# Controllboard.net
KiCad netlist of a schematic drawn in EAGLE
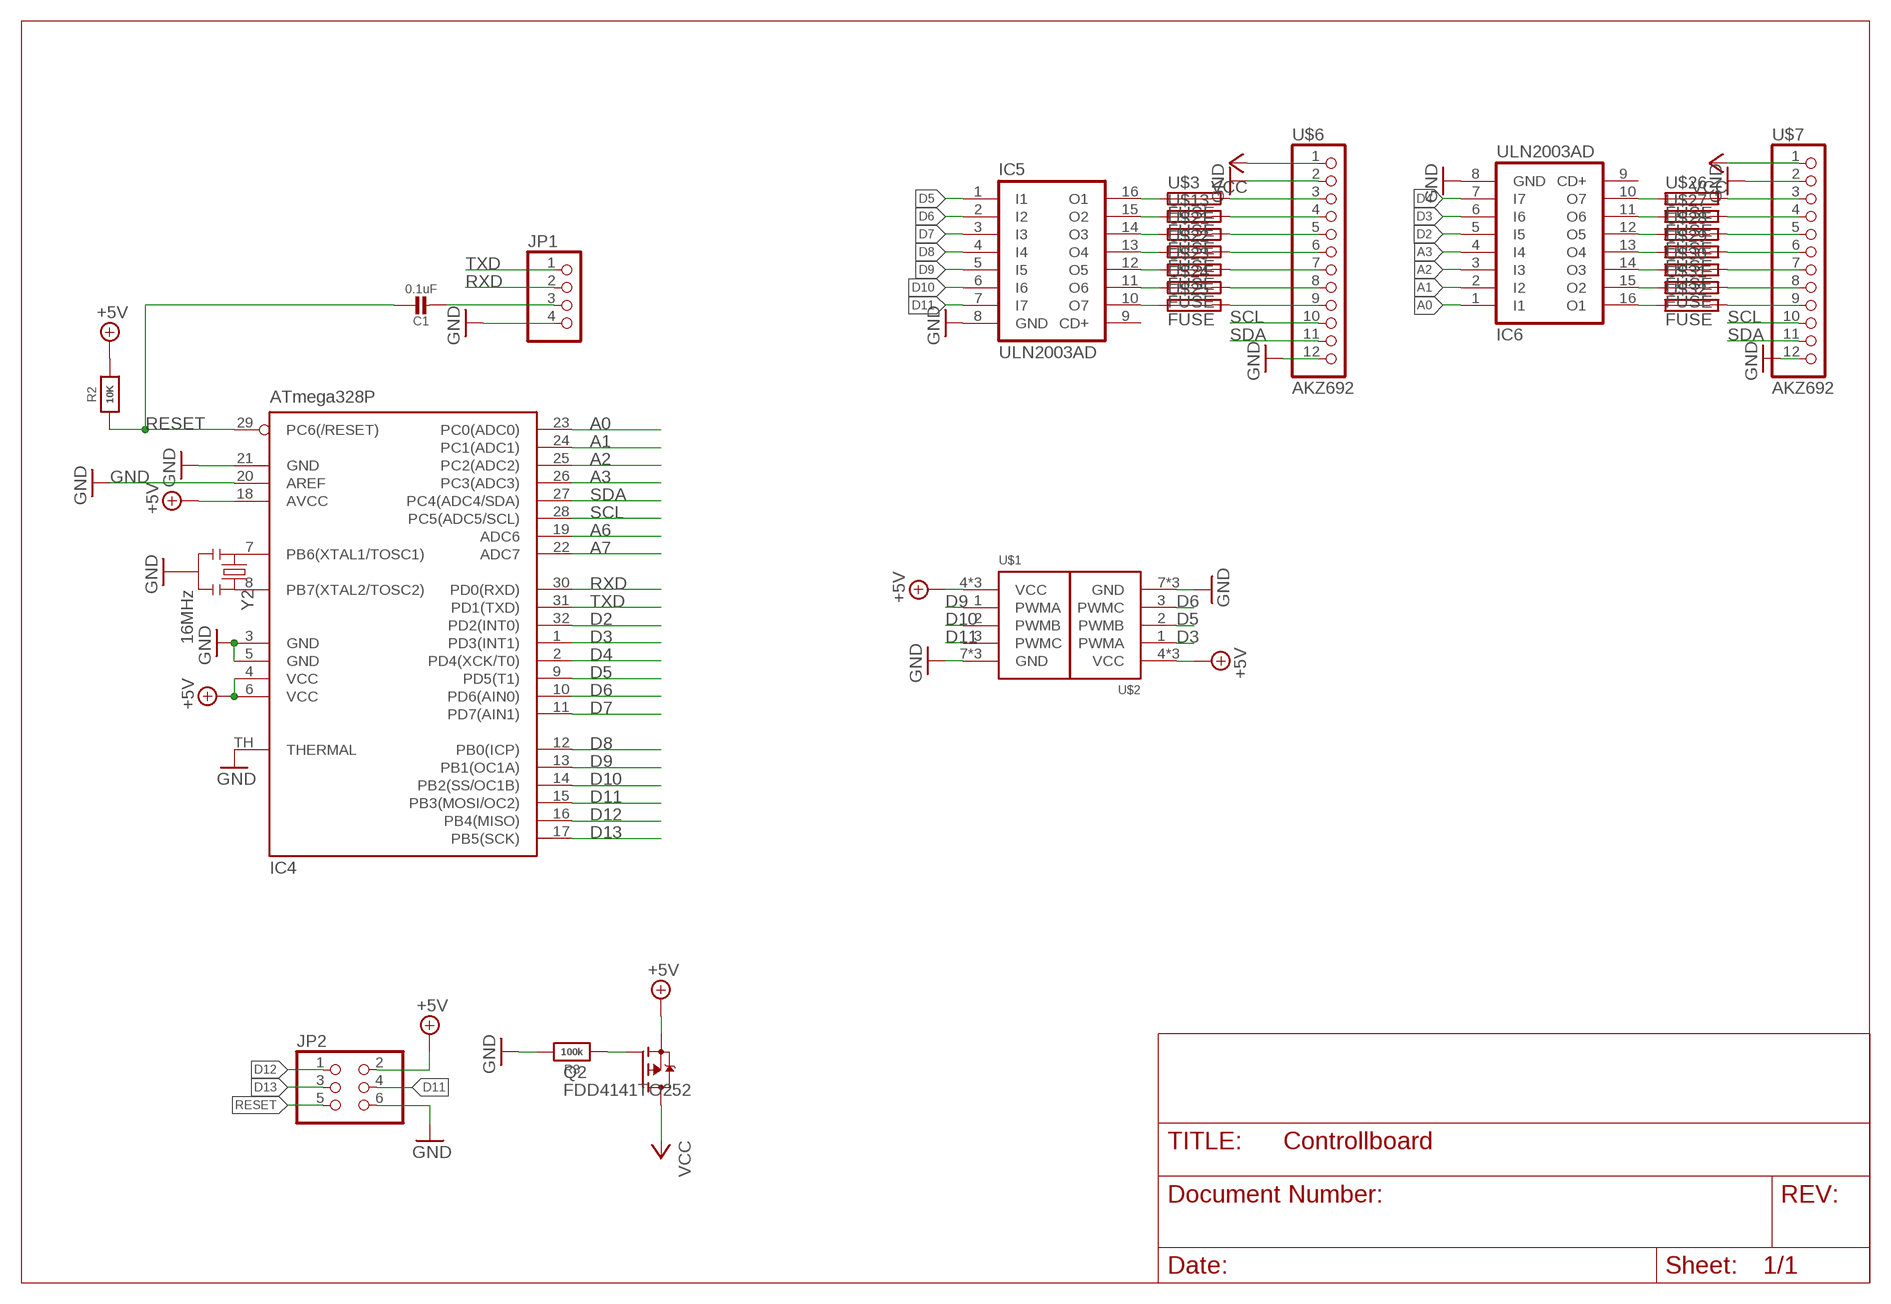
[diagram p0: schematic, sheet 1]

(export (version "E")
  (design (tool "Eeschema 10.0.6"))
  (components
    (comp (ref "C1")
      (value "0.1uF")
      (footprint "eagle-import:0805-NO")
      (libsource (lib "eagle-import") (part "CAP_CERAMIC0805-NOOUTLINE"))
    )
    (comp (ref "IC4")
      (value "ATmega328P")
      (footprint "eagle-import:MLF32-TH")
      (fields (field (name "MPN") "ATMEGA88PA-MU"))
      (libsource (lib "eagle-import") (part "MEGA8-MI"))
    )
    (comp (ref "IC5")
      (value "ULN2003AD")
      (footprint "eagle-import:SO16")
      (libsource (lib "eagle-import") (part "ULN2003AD"))
    )
    (comp (ref "IC6")
      (value "ULN2003AD")
      (footprint "eagle-import:SO16")
      (libsource (lib "eagle-import") (part "ULN2003AD"))
    )
    (comp (ref "JP1")
      (value "PINHD-1X4")
      (footprint "eagle-import:1X04")
      (libsource (lib "eagle-import") (part "PINHD-1X4"))
    )
    (comp (ref "JP2")
      (value "PINHD-2X3M")
      (footprint "eagle-import:2X03M")
      (libsource (lib "eagle-import") (part "PINHD-2X3M"))
    )
    (comp (ref "Q2")
      (value "FDD4141TO252")
      (footprint "eagle-import:TO252")
      (libsource (lib "eagle-import") (part "FDD4141TO252"))
    )
    (comp (ref "R2")
      (value "10K")
      (footprint "eagle-import:0805-NO")
      (libsource (lib "eagle-import") (part "RESISTOR0805_NOOUTLINE"))
    )
    (comp (ref "R3")
      (value "100k")
      (footprint "eagle-import:0805-NO")
      (libsource (lib "eagle-import") (part "RESISTOR0805_NOOUTLINE"))
    )
    (comp (ref "U$1")
      (value "SERVO_X3")
      (footprint "eagle-import:2X03_90")
      (libsource (lib "eagle-import") (part "SERVO_X3"))
    )
    (comp (ref "U$2")
      (value "SERVO_X3")
      (footprint "eagle-import:2X03_90")
      (libsource (lib "eagle-import") (part "SERVO_X3"))
    )
    (comp (ref "U$3")
      (value "FUSE")
      (footprint "eagle-import:C1206")
      (libsource (lib "eagle-import") (part "FUSE"))
    )
    (comp (ref "U$6")
      (value "AKZ692")
      (footprint "eagle-import:1X12")
      (libsource (lib "eagle-import") (part "AKZ692"))
    )
    (comp (ref "U$7")
      (value "AKZ692")
      (footprint "eagle-import:1X12")
      (libsource (lib "eagle-import") (part "AKZ692"))
    )
    (comp (ref "U$13")
      (value "FUSE")
      (footprint "eagle-import:C1206")
      (libsource (lib "eagle-import") (part "FUSE"))
    )
    (comp (ref "U$21")
      (value "FUSE")
      (footprint "eagle-import:C1206")
      (libsource (lib "eagle-import") (part "FUSE"))
    )
    (comp (ref "U$22")
      (value "FUSE")
      (footprint "eagle-import:C1206")
      (libsource (lib "eagle-import") (part "FUSE"))
    )
    (comp (ref "U$23")
      (value "FUSE")
      (footprint "eagle-import:C1206")
      (libsource (lib "eagle-import") (part "FUSE"))
    )
    (comp (ref "U$24")
      (value "FUSE")
      (footprint "eagle-import:C1206")
      (libsource (lib "eagle-import") (part "FUSE"))
    )
    (comp (ref "U$25")
      (value "FUSE")
      (footprint "eagle-import:C1206")
      (libsource (lib "eagle-import") (part "FUSE"))
    )
    (comp (ref "U$26")
      (value "FUSE")
      (footprint "eagle-import:C1206")
      (libsource (lib "eagle-import") (part "FUSE"))
    )
    (comp (ref "U$27")
      (value "FUSE")
      (footprint "eagle-import:C1206")
      (libsource (lib "eagle-import") (part "FUSE"))
    )
    (comp (ref "U$28")
      (value "FUSE")
      (footprint "eagle-import:C1206")
      (libsource (lib "eagle-import") (part "FUSE"))
    )
    (comp (ref "U$29")
      (value "FUSE")
      (footprint "eagle-import:C1206")
      (libsource (lib "eagle-import") (part "FUSE"))
    )
    (comp (ref "U$30")
      (value "FUSE")
      (footprint "eagle-import:C1206")
      (libsource (lib "eagle-import") (part "FUSE"))
    )
    (comp (ref "U$31")
      (value "FUSE")
      (footprint "eagle-import:C1206")
      (libsource (lib "eagle-import") (part "FUSE"))
    )
    (comp (ref "U$32")
      (value "FUSE")
      (footprint "eagle-import:C1206")
      (libsource (lib "eagle-import") (part "FUSE"))
    )
    (comp (ref "Y2")
      (value "16MHz")
      (footprint "eagle-import:RESONATOR-SMD")
      (libsource (lib "eagle-import") (part "RESONATORSMD"))
    )
  )
  (nets
    (net (code "1") (name "+5V") (class "Default")
      (node (ref "IC4") (pin "18") (pinfunction "AVCC_18") (pintype "power_in"))
      (node (ref "IC4") (pin "4") (pinfunction "VCC_4") (pintype "power_in"))
      (node (ref "IC4") (pin "6") (pinfunction "VCC_6") (pintype "power_in"))
      (node (ref "JP2") (pin "2") (pinfunction "2_2") (pintype "passive"))
      (node (ref "Q2") (pin "2") (pinfunction "S_2") (pintype "passive"))
      (node (ref "R2") (pin "2") (pinfunction "2_2") (pintype "passive"))
      (node (ref "U$1") (pin "4") (pinfunction "VCC_4") (pintype "bidirectional"))
      (node (ref "U$1") (pin "5") (pinfunction "VCC_5") (pintype "bidirectional"))
      (node (ref "U$1") (pin "6") (pinfunction "VCC_6") (pintype "bidirectional"))
      (node (ref "U$2") (pin "4") (pinfunction "VCC_4") (pintype "bidirectional"))
      (node (ref "U$2") (pin "5") (pinfunction "VCC_5") (pintype "bidirectional"))
      (node (ref "U$2") (pin "6") (pinfunction "VCC_6") (pintype "bidirectional"))
    )
    (net (code "2") (name "/A6") (class "Default")
      (node (ref "IC4") (pin "19") (pinfunction "ADC6_19") (pintype "bidirectional"))
    )
    (net (code "3") (name "/A7") (class "Default")
      (node (ref "IC4") (pin "22") (pinfunction "ADC7_22") (pintype "bidirectional"))
    )
    (net (code "4") (name "/RXD") (class "Default")
      (node (ref "IC4") (pin "30") (pinfunction "PD0(RXD)_30") (pintype "bidirectional"))
      (node (ref "JP1") (pin "2") (pinfunction "2_2") (pintype "passive"))
    )
    (net (code "5") (name "/SCL") (class "Default")
      (node (ref "IC4") (pin "28") (pinfunction "PC5(ADC5/SCL)_28") (pintype "bidirectional"))
      (node (ref "U$6") (pin "10") (pinfunction "10_10") (pintype "passive"))
      (node (ref "U$7") (pin "10") (pinfunction "10_10") (pintype "passive"))
    )
    (net (code "6") (name "/SDA") (class "Default")
      (node (ref "IC4") (pin "27") (pinfunction "PC4(ADC4/SDA)_27") (pintype "bidirectional"))
      (node (ref "U$6") (pin "11") (pinfunction "11_11") (pintype "passive"))
      (node (ref "U$7") (pin "11") (pinfunction "11_11") (pintype "passive"))
    )
    (net (code "7") (name "/TXD") (class "Default")
      (node (ref "IC4") (pin "31") (pinfunction "PD1(TXD)_31") (pintype "bidirectional"))
      (node (ref "JP1") (pin "1") (pinfunction "1_1") (pintype "passive"))
    )
    (net (code "8") (name "A0") (class "Default")
      (node (ref "IC4") (pin "23") (pinfunction "PC0(ADC0)_23") (pintype "bidirectional"))
      (node (ref "IC6") (pin "1") (pinfunction "I1_1") (pintype "input"))
    )
    (net (code "9") (name "A1") (class "Default")
      (node (ref "IC4") (pin "24") (pinfunction "PC1(ADC1)_24") (pintype "bidirectional"))
      (node (ref "IC6") (pin "2") (pinfunction "I2_2") (pintype "input"))
    )
    (net (code "10") (name "A2") (class "Default")
      (node (ref "IC4") (pin "25") (pinfunction "PC2(ADC2)_25") (pintype "bidirectional"))
      (node (ref "IC6") (pin "3") (pinfunction "I3_3") (pintype "input"))
    )
    (net (code "11") (name "A3") (class "Default")
      (node (ref "IC4") (pin "26") (pinfunction "PC3(ADC3)_26") (pintype "bidirectional"))
      (node (ref "IC6") (pin "4") (pinfunction "I4_4") (pintype "input"))
    )
    (net (code "12") (name "D2") (class "Default")
      (node (ref "IC4") (pin "32") (pinfunction "PD2(INT0)_32") (pintype "bidirectional"))
      (node (ref "IC6") (pin "5") (pinfunction "I5_5") (pintype "input"))
    )
    (net (code "13") (name "D3") (class "Default")
      (node (ref "IC4") (pin "1") (pinfunction "PD3(INT1)_1") (pintype "bidirectional"))
      (node (ref "IC6") (pin "6") (pinfunction "I6_6") (pintype "input"))
      (node (ref "U$2") (pin "1") (pinfunction "PWMA_1") (pintype "bidirectional"))
    )
    (net (code "14") (name "D4") (class "Default")
      (node (ref "IC4") (pin "2") (pinfunction "PD4(XCK/T0)_2") (pintype "bidirectional"))
      (node (ref "IC6") (pin "7") (pinfunction "I7_7") (pintype "input"))
    )
    (net (code "15") (name "D5") (class "Default")
      (node (ref "IC4") (pin "9") (pinfunction "PD5(T1)_9") (pintype "bidirectional"))
      (node (ref "IC5") (pin "1") (pinfunction "I1_1") (pintype "input"))
      (node (ref "U$2") (pin "2") (pinfunction "PWMB_2") (pintype "bidirectional"))
    )
    (net (code "16") (name "D6") (class "Default")
      (node (ref "IC4") (pin "10") (pinfunction "PD6(AIN0)_10") (pintype "bidirectional"))
      (node (ref "IC5") (pin "2") (pinfunction "I2_2") (pintype "input"))
      (node (ref "U$2") (pin "3") (pinfunction "PWMC_3") (pintype "bidirectional"))
    )
    (net (code "17") (name "D7") (class "Default")
      (node (ref "IC4") (pin "11") (pinfunction "PD7(AIN1)_11") (pintype "bidirectional"))
      (node (ref "IC5") (pin "3") (pinfunction "I3_3") (pintype "input"))
    )
    (net (code "18") (name "D8") (class "Default")
      (node (ref "IC4") (pin "12") (pinfunction "PB0(ICP)_12") (pintype "bidirectional"))
      (node (ref "IC5") (pin "4") (pinfunction "I4_4") (pintype "input"))
    )
    (net (code "19") (name "D9") (class "Default")
      (node (ref "IC4") (pin "13") (pinfunction "PB1(OC1A)_13") (pintype "bidirectional"))
      (node (ref "IC5") (pin "5") (pinfunction "I5_5") (pintype "input"))
      (node (ref "U$1") (pin "1") (pinfunction "PWMA_1") (pintype "bidirectional"))
    )
    (net (code "20") (name "D10") (class "Default")
      (node (ref "IC4") (pin "14") (pinfunction "PB2(SS/OC1B)_14") (pintype "bidirectional"))
      (node (ref "IC5") (pin "6") (pinfunction "I6_6") (pintype "input"))
      (node (ref "U$1") (pin "2") (pinfunction "PWMB_2") (pintype "bidirectional"))
    )
    (net (code "21") (name "D11") (class "Default")
      (node (ref "IC4") (pin "15") (pinfunction "PB3(MOSI/OC2)_15") (pintype "bidirectional"))
      (node (ref "IC5") (pin "7") (pinfunction "I7_7") (pintype "input"))
      (node (ref "JP2") (pin "4") (pinfunction "4_4") (pintype "passive"))
      (node (ref "U$1") (pin "3") (pinfunction "PWMC_3") (pintype "bidirectional"))
    )
    (net (code "22") (name "D12") (class "Default")
      (node (ref "IC4") (pin "16") (pinfunction "PB4(MISO)_16") (pintype "bidirectional"))
      (node (ref "JP2") (pin "1") (pinfunction "1_1") (pintype "passive"))
    )
    (net (code "23") (name "D13") (class "Default")
      (node (ref "IC4") (pin "17") (pinfunction "PB5(SCK)_17") (pintype "bidirectional"))
      (node (ref "JP2") (pin "3") (pinfunction "3_3") (pintype "passive"))
    )
    (net (code "24") (name "GND") (class "Default")
      (node (ref "IC4") (pin "20") (pinfunction "AREF_20") (pintype "passive"))
      (node (ref "IC4") (pin "21") (pinfunction "GND_21") (pintype "power_in"))
      (node (ref "IC4") (pin "3") (pinfunction "GND_3") (pintype "power_in"))
      (node (ref "IC4") (pin "5") (pinfunction "GND_5") (pintype "power_in"))
      (node (ref "IC4") (pin "TH") (pinfunction "THERMAL_TH") (pintype "passive"))
      (node (ref "IC5") (pin "8") (pinfunction "GND_8") (pintype "power_in"))
      (node (ref "IC6") (pin "8") (pinfunction "GND_8") (pintype "power_in"))
      (node (ref "JP1") (pin "4") (pinfunction "4_4") (pintype "passive"))
      (node (ref "JP2") (pin "6") (pinfunction "6_6") (pintype "passive"))
      (node (ref "R3") (pin "2") (pinfunction "2_2") (pintype "passive"))
      (node (ref "U$1") (pin "7") (pinfunction "GND_7") (pintype "bidirectional"))
      (node (ref "U$1") (pin "8") (pinfunction "GND_8") (pintype "bidirectional"))
      (node (ref "U$1") (pin "9") (pinfunction "GND_9") (pintype "bidirectional"))
      (node (ref "U$2") (pin "7") (pinfunction "GND_7") (pintype "bidirectional"))
      (node (ref "U$2") (pin "8") (pinfunction "GND_8") (pintype "bidirectional"))
      (node (ref "U$2") (pin "9") (pinfunction "GND_9") (pintype "bidirectional"))
      (node (ref "U$6") (pin "12") (pinfunction "12_12") (pintype "passive"))
      (node (ref "U$6") (pin "2") (pinfunction "2_2") (pintype "passive"))
      (node (ref "U$7") (pin "12") (pinfunction "12_12") (pintype "passive"))
      (node (ref "U$7") (pin "2") (pinfunction "2_2") (pintype "passive"))
      (node (ref "Y2") (pin "2") (pinfunction "2_2") (pintype "passive"))
    )
    (net (code "25") (name "Net-(C1-Pad2)") (class "Default")
      (node (ref "C1") (pin "2") (pinfunction "2_2") (pintype "passive"))
      (node (ref "JP1") (pin "3") (pinfunction "3_3") (pintype "passive"))
    )
    (net (code "26") (name "Net-(IC4-PB6(XTAL1{slash}TOSC1))") (class "Default")
      (node (ref "IC4") (pin "7") (pinfunction "PB6(XTAL1/TOSC1)_7") (pintype "bidirectional"))
      (node (ref "Y2") (pin "1") (pinfunction "1_1") (pintype "passive"))
    )
    (net (code "27") (name "Net-(IC4-PB7(XTAL2{slash}TOSC2))") (class "Default")
      (node (ref "IC4") (pin "8") (pinfunction "PB7(XTAL2/TOSC2)_8") (pintype "bidirectional"))
      (node (ref "Y2") (pin "3") (pinfunction "3_3") (pintype "passive"))
    )
    (net (code "28") (name "Net-(IC5-O1)") (class "Default")
      (node (ref "IC5") (pin "16") (pinfunction "O1_16") (pintype "open_collector"))
      (node (ref "U$3") (pin "1") (pinfunction "1_1") (pintype "passive"))
    )
    (net (code "29") (name "Net-(IC5-O2)") (class "Default")
      (node (ref "IC5") (pin "15") (pinfunction "O2_15") (pintype "open_collector"))
      (node (ref "U$13") (pin "1") (pinfunction "1_1") (pintype "passive"))
    )
    (net (code "30") (name "Net-(IC5-O3)") (class "Default")
      (node (ref "IC5") (pin "14") (pinfunction "O3_14") (pintype "open_collector"))
      (node (ref "U$21") (pin "1") (pinfunction "1_1") (pintype "passive"))
    )
    (net (code "31") (name "Net-(IC5-O4)") (class "Default")
      (node (ref "IC5") (pin "13") (pinfunction "O4_13") (pintype "open_collector"))
      (node (ref "U$22") (pin "1") (pinfunction "1_1") (pintype "passive"))
    )
    (net (code "32") (name "Net-(IC5-O5)") (class "Default")
      (node (ref "IC5") (pin "12") (pinfunction "O5_12") (pintype "open_collector"))
      (node (ref "U$23") (pin "1") (pinfunction "1_1") (pintype "passive"))
    )
    (net (code "33") (name "Net-(IC5-O6)") (class "Default")
      (node (ref "IC5") (pin "11") (pinfunction "O6_11") (pintype "open_collector"))
      (node (ref "U$24") (pin "1") (pinfunction "1_1") (pintype "passive"))
    )
    (net (code "34") (name "Net-(IC5-O7)") (class "Default")
      (node (ref "IC5") (pin "10") (pinfunction "O7_10") (pintype "open_collector"))
      (node (ref "U$25") (pin "1") (pinfunction "1_1") (pintype "passive"))
    )
    (net (code "35") (name "Net-(IC6-O1)") (class "Default")
      (node (ref "IC6") (pin "16") (pinfunction "O1_16") (pintype "open_collector"))
      (node (ref "U$32") (pin "1") (pinfunction "1_1") (pintype "passive"))
    )
    (net (code "36") (name "Net-(IC6-O2)") (class "Default")
      (node (ref "IC6") (pin "15") (pinfunction "O2_15") (pintype "open_collector"))
      (node (ref "U$31") (pin "1") (pinfunction "1_1") (pintype "passive"))
    )
    (net (code "37") (name "Net-(IC6-O3)") (class "Default")
      (node (ref "IC6") (pin "14") (pinfunction "O3_14") (pintype "open_collector"))
      (node (ref "U$30") (pin "1") (pinfunction "1_1") (pintype "passive"))
    )
    (net (code "38") (name "Net-(IC6-O4)") (class "Default")
      (node (ref "IC6") (pin "13") (pinfunction "O4_13") (pintype "open_collector"))
      (node (ref "U$29") (pin "1") (pinfunction "1_1") (pintype "passive"))
    )
    (net (code "39") (name "Net-(IC6-O5)") (class "Default")
      (node (ref "IC6") (pin "12") (pinfunction "O5_12") (pintype "open_collector"))
      (node (ref "U$28") (pin "1") (pinfunction "1_1") (pintype "passive"))
    )
    (net (code "40") (name "Net-(IC6-O6)") (class "Default")
      (node (ref "IC6") (pin "11") (pinfunction "O6_11") (pintype "open_collector"))
      (node (ref "U$27") (pin "1") (pinfunction "1_1") (pintype "passive"))
    )
    (net (code "41") (name "Net-(IC6-O7)") (class "Default")
      (node (ref "IC6") (pin "10") (pinfunction "O7_10") (pintype "open_collector"))
      (node (ref "U$26") (pin "1") (pinfunction "1_1") (pintype "passive"))
    )
    (net (code "42") (name "Net-(Q2-G)") (class "Default")
      (node (ref "Q2") (pin "1") (pinfunction "G_1") (pintype "passive"))
      (node (ref "R3") (pin "1") (pinfunction "1_1") (pintype "passive"))
    )
    (net (code "43") (name "Net-(U$3-Pad2)") (class "Default")
      (node (ref "U$3") (pin "2") (pinfunction "2_2") (pintype "passive"))
      (node (ref "U$6") (pin "3") (pinfunction "3_3") (pintype "passive"))
    )
    (net (code "44") (name "Net-(U$13-Pad2)") (class "Default")
      (node (ref "U$13") (pin "2") (pinfunction "2_2") (pintype "passive"))
      (node (ref "U$6") (pin "4") (pinfunction "4_4") (pintype "passive"))
    )
    (net (code "45") (name "Net-(U$21-Pad2)") (class "Default")
      (node (ref "U$21") (pin "2") (pinfunction "2_2") (pintype "passive"))
      (node (ref "U$6") (pin "5") (pinfunction "5_5") (pintype "passive"))
    )
    (net (code "46") (name "Net-(U$22-Pad2)") (class "Default")
      (node (ref "U$22") (pin "2") (pinfunction "2_2") (pintype "passive"))
      (node (ref "U$6") (pin "6") (pinfunction "6_6") (pintype "passive"))
    )
    (net (code "47") (name "Net-(U$23-Pad2)") (class "Default")
      (node (ref "U$23") (pin "2") (pinfunction "2_2") (pintype "passive"))
      (node (ref "U$6") (pin "7") (pinfunction "7_7") (pintype "passive"))
    )
    (net (code "48") (name "Net-(U$24-Pad2)") (class "Default")
      (node (ref "U$24") (pin "2") (pinfunction "2_2") (pintype "passive"))
      (node (ref "U$6") (pin "8") (pinfunction "8_8") (pintype "passive"))
    )
    (net (code "49") (name "Net-(U$25-Pad2)") (class "Default")
      (node (ref "U$25") (pin "2") (pinfunction "2_2") (pintype "passive"))
      (node (ref "U$6") (pin "9") (pinfunction "9_9") (pintype "passive"))
    )
    (net (code "50") (name "Net-(U$26-Pad2)") (class "Default")
      (node (ref "U$26") (pin "2") (pinfunction "2_2") (pintype "passive"))
      (node (ref "U$7") (pin "3") (pinfunction "3_3") (pintype "passive"))
    )
    (net (code "51") (name "Net-(U$27-Pad2)") (class "Default")
      (node (ref "U$27") (pin "2") (pinfunction "2_2") (pintype "passive"))
      (node (ref "U$7") (pin "4") (pinfunction "4_4") (pintype "passive"))
    )
    (net (code "52") (name "Net-(U$28-Pad2)") (class "Default")
      (node (ref "U$28") (pin "2") (pinfunction "2_2") (pintype "passive"))
      (node (ref "U$7") (pin "5") (pinfunction "5_5") (pintype "passive"))
    )
    (net (code "53") (name "Net-(U$29-Pad2)") (class "Default")
      (node (ref "U$29") (pin "2") (pinfunction "2_2") (pintype "passive"))
      (node (ref "U$7") (pin "6") (pinfunction "6_6") (pintype "passive"))
    )
    (net (code "54") (name "Net-(U$30-Pad2)") (class "Default")
      (node (ref "U$30") (pin "2") (pinfunction "2_2") (pintype "passive"))
      (node (ref "U$7") (pin "7") (pinfunction "7_7") (pintype "passive"))
    )
    (net (code "55") (name "Net-(U$31-Pad2)") (class "Default")
      (node (ref "U$31") (pin "2") (pinfunction "2_2") (pintype "passive"))
      (node (ref "U$7") (pin "8") (pinfunction "8_8") (pintype "passive"))
    )
    (net (code "56") (name "Net-(U$32-Pad2)") (class "Default")
      (node (ref "U$32") (pin "2") (pinfunction "2_2") (pintype "passive"))
      (node (ref "U$7") (pin "9") (pinfunction "9_9") (pintype "passive"))
    )
    (net (code "57") (name "RESET") (class "Default")
      (node (ref "C1") (pin "1") (pinfunction "1_1") (pintype "passive"))
      (node (ref "IC4") (pin "29") (pinfunction "PC6(/RESET)_29") (pintype "bidirectional"))
      (node (ref "JP2") (pin "5") (pinfunction "5_5") (pintype "passive"))
      (node (ref "R2") (pin "1") (pinfunction "1_1") (pintype "passive"))
    )
    (net (code "58") (name "VCC") (class "Default")
      (node (ref "Q2") (pin "3") (pinfunction "D_3") (pintype "passive"))
      (node (ref "U$6") (pin "1") (pinfunction "1_1") (pintype "passive"))
      (node (ref "U$7") (pin "1") (pinfunction "1_1") (pintype "passive"))
    )
    (net (code "59") (name "unconnected-(IC5-CD+-Pad9)") (class "Default")
      (node (ref "IC5") (pin "9") (pinfunction "CD+_9") (pintype "passive"))
    )
    (net (code "60") (name "unconnected-(IC6-CD+-Pad9)") (class "Default")
      (node (ref "IC6") (pin "9") (pinfunction "CD+_9") (pintype "passive"))
    )
  )
)
